# SoC_PWR.net
KiCad netlist of a schematic drawn in Altium Designer
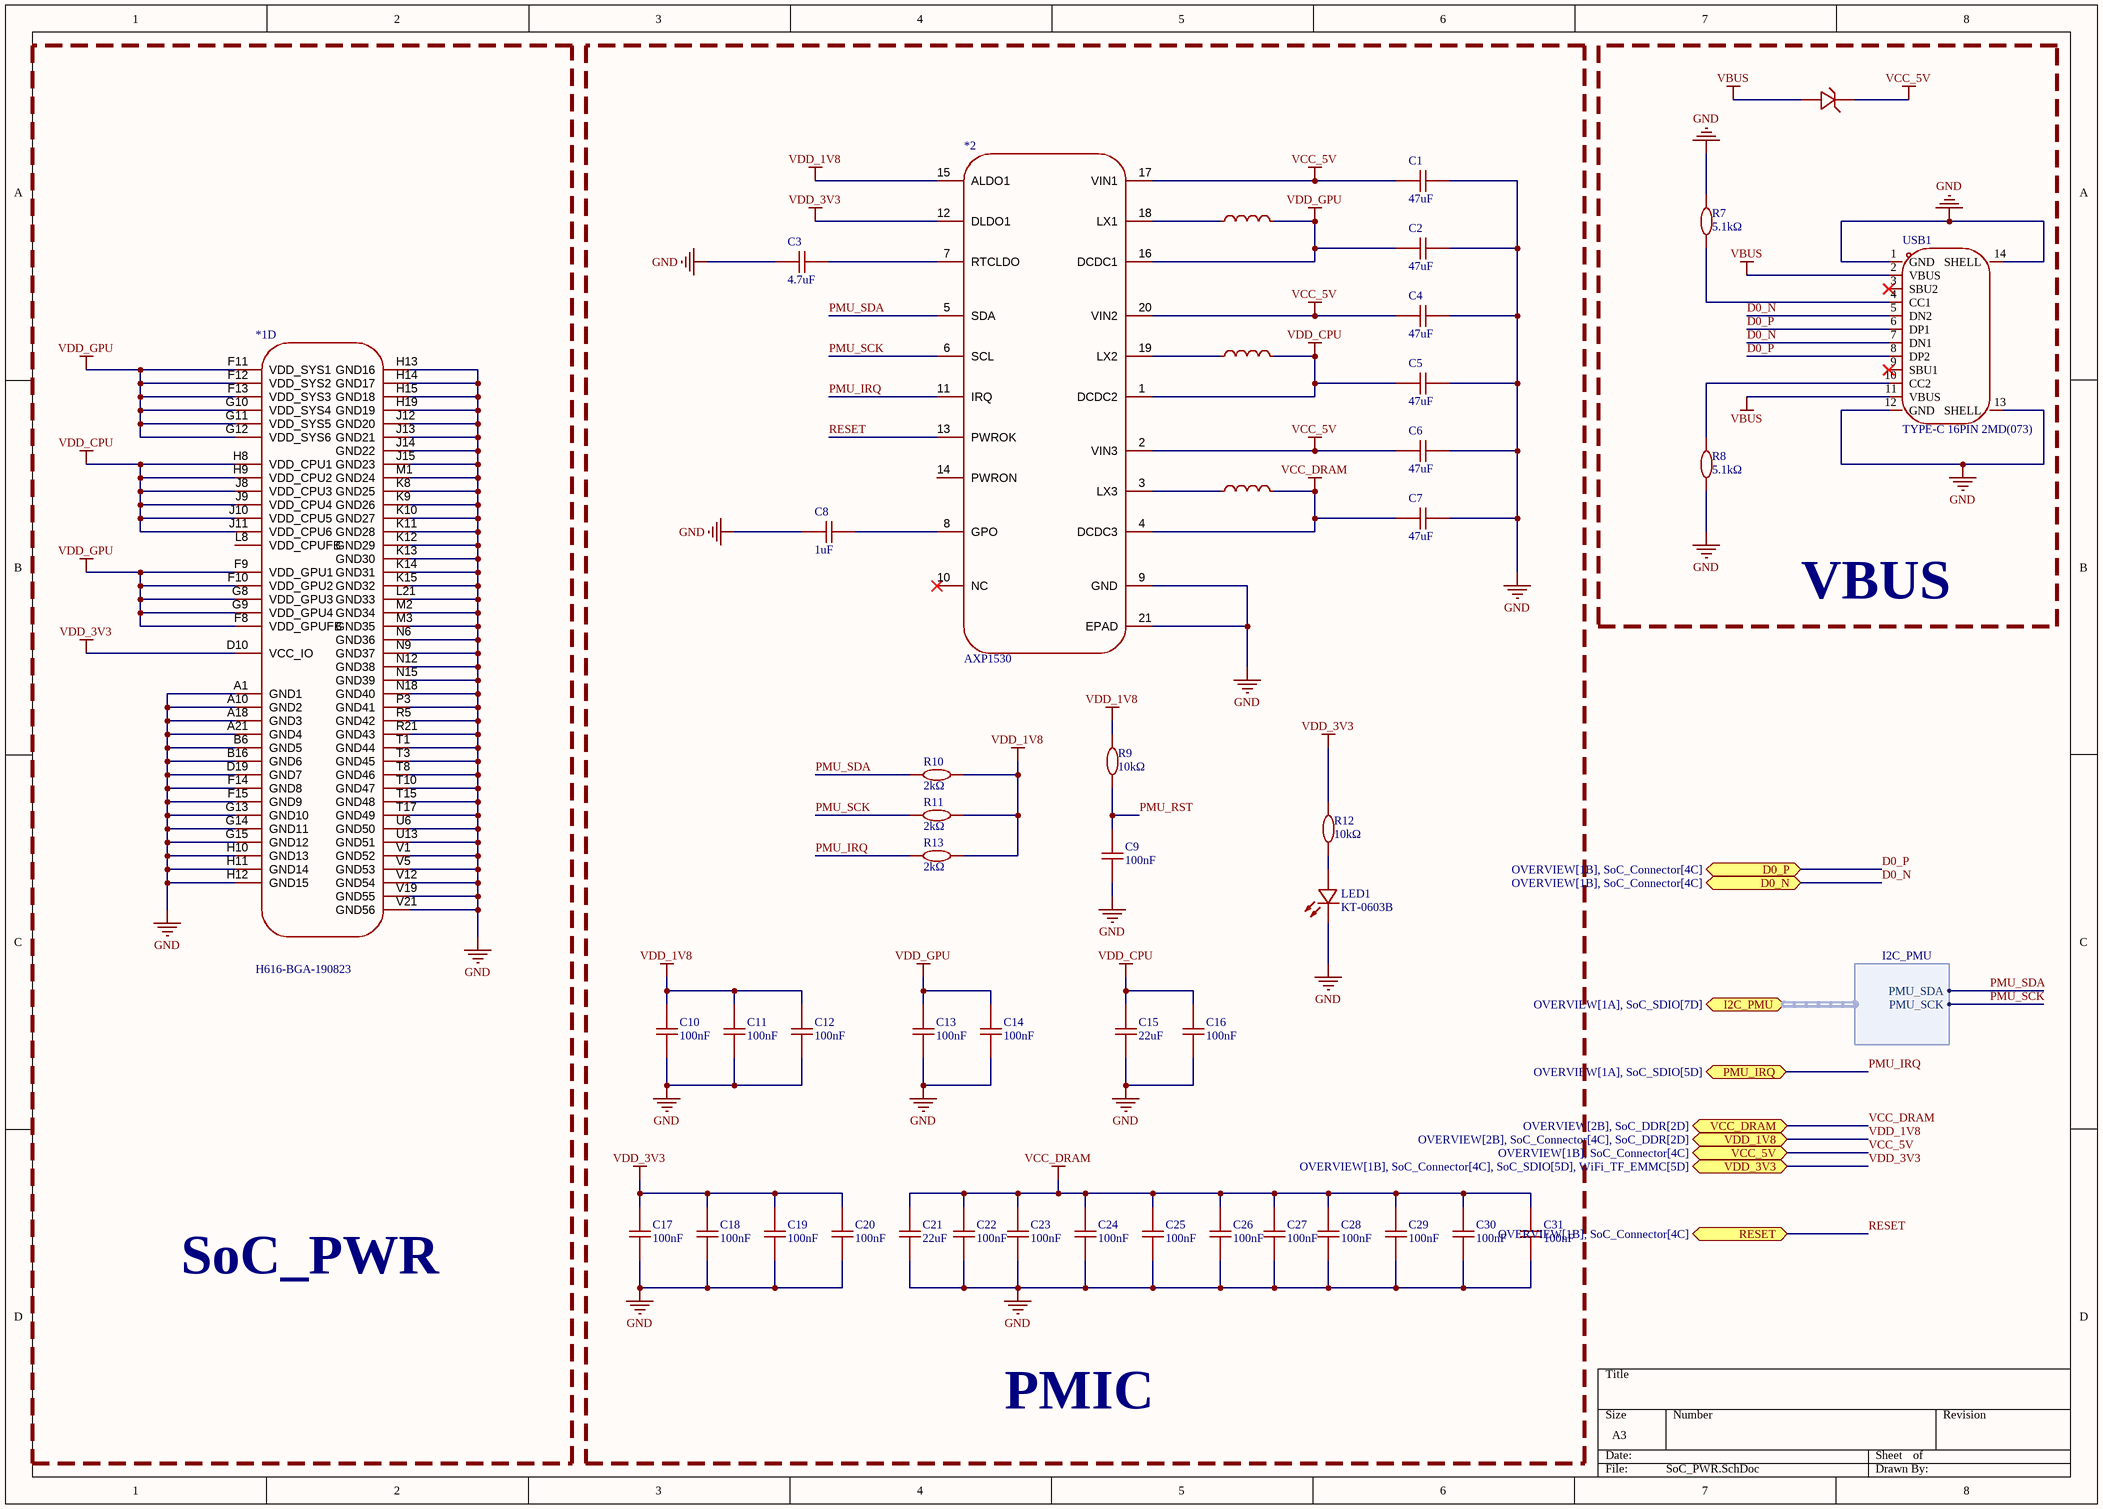
[diagram p0: SoC_PWR.SchDoc]

(export (version "E")
  (design (tool "Eeschema 10.0.6"))
  (components
    (comp (ref "*1")
      (value "H616-BGA-190823")
      (footprint "BGA-284_L14.0-W12.0-P0.65-TL")
      (description "Allwinner H616")
      (libsource (lib "IC") (part "H616-BGA-190823"))
    )
    (comp (ref "*2")
      (value "AXP1530")
      (footprint "QFN-20_L3.0-W3.0-P0.40-BL-EP1.7")
      (description "AXP313A")
      (libsource (lib "IC") (part "AXP1530"))
    )
    (comp (ref "C1")
      (value "47uF")
      (footprint "C0603")
      (description "16V 22uF X5R ±20% 0603 Ceramic Capacitors ROHS")
      (libsource (lib "RLC") (part "47uF"))
    )
    (comp (ref "C2")
      (value "47uF")
      (footprint "C0603")
      (description "16V 22uF X5R ±20% 0603 Ceramic Capacitors ROHS")
      (libsource (lib "RLC") (part "47uF"))
    )
    (comp (ref "C3")
      (value "4.7uF")
      (footprint "C0402")
      (description "10V 4.7uF X5R ±20% 0402 Ceramic Capacitors ROHS")
      (libsource (lib "RLC") (part "4.7uF"))
    )
    (comp (ref "C4")
      (value "47uF")
      (footprint "C0603")
      (description "16V 22uF X5R ±20% 0603 Ceramic Capacitors ROHS")
      (libsource (lib "RLC") (part "47uF"))
    )
    (comp (ref "C5")
      (value "47uF")
      (footprint "C0603")
      (description "16V 22uF X5R ±20% 0603 Ceramic Capacitors ROHS")
      (libsource (lib "RLC") (part "47uF"))
    )
    (comp (ref "C6")
      (value "47uF")
      (footprint "C0603")
      (description "16V 22uF X5R ±20% 0603 Ceramic Capacitors ROHS")
      (libsource (lib "RLC") (part "47uF"))
    )
    (comp (ref "C7")
      (value "47uF")
      (footprint "C0603")
      (description "16V 22uF X5R ±20% 0603 Ceramic Capacitors ROHS")
      (libsource (lib "RLC") (part "47uF"))
    )
    (comp (ref "C8")
      (value "1uF")
      (footprint "C0402")
      (description "50V 1uF X5R ±10% 0402 Ceramic Capacitors ROHS")
      (libsource (lib "RLC") (part "1uF"))
    )
    (comp (ref "C9")
      (value "100nF")
      (footprint "C0402")
      (description "50V 100nF X7R ±10% 0402 Ceramic Capacitors ROHS")
      (libsource (lib "RLC") (part "100nF"))
    )
    (comp (ref "C10")
      (value "100nF")
      (footprint "C0402")
      (description "50V 100nF X7R ±10% 0402 Ceramic Capacitors ROHS")
      (libsource (lib "RLC") (part "100nF"))
    )
    (comp (ref "C11")
      (value "100nF")
      (footprint "C0402")
      (description "50V 100nF X7R ±10% 0402 Ceramic Capacitors ROHS")
      (libsource (lib "RLC") (part "100nF"))
    )
    (comp (ref "C12")
      (value "100nF")
      (footprint "C0402")
      (description "50V 100nF X7R ±10% 0402 Ceramic Capacitors ROHS")
      (libsource (lib "RLC") (part "100nF"))
    )
    (comp (ref "C13")
      (value "100nF")
      (footprint "C0402")
      (description "50V 100nF X7R ±10% 0402 Ceramic Capacitors ROHS")
      (libsource (lib "RLC") (part "100nF"))
    )
    (comp (ref "C14")
      (value "100nF")
      (footprint "C0402")
      (description "50V 100nF X7R ±10% 0402 Ceramic Capacitors ROHS")
      (libsource (lib "RLC") (part "100nF"))
    )
    (comp (ref "C15")
      (value "22uF")
      (footprint "C0603")
      (description "16V 22uF X5R ±20% 0603 Ceramic Capacitors ROHS")
      (libsource (lib "RLC") (part "22uF"))
    )
    (comp (ref "C16")
      (value "100nF")
      (footprint "C0402")
      (description "50V 100nF X7R ±10% 0402 Ceramic Capacitors ROHS")
      (libsource (lib "RLC") (part "100nF"))
    )
    (comp (ref "C17")
      (value "100nF")
      (footprint "C0402")
      (description "50V 100nF X7R ±10% 0402 Ceramic Capacitors ROHS")
      (libsource (lib "RLC") (part "100nF"))
    )
    (comp (ref "C18")
      (value "100nF")
      (footprint "C0402")
      (description "50V 100nF X7R ±10% 0402 Ceramic Capacitors ROHS")
      (libsource (lib "RLC") (part "100nF"))
    )
    (comp (ref "C19")
      (value "100nF")
      (footprint "C0402")
      (description "50V 100nF X7R ±10% 0402 Ceramic Capacitors ROHS")
      (libsource (lib "RLC") (part "100nF"))
    )
    (comp (ref "C20")
      (value "100nF")
      (footprint "C0402")
      (description "50V 100nF X7R ±10% 0402 Ceramic Capacitors ROHS")
      (libsource (lib "RLC") (part "100nF"))
    )
    (comp (ref "C21")
      (value "22uF")
      (footprint "C0603")
      (description "16V 22uF X5R ±20% 0603 Ceramic Capacitors ROHS")
      (libsource (lib "RLC") (part "22uF"))
    )
    (comp (ref "C22")
      (value "100nF")
      (footprint "C0402")
      (description "50V 100nF X7R ±10% 0402 Ceramic Capacitors ROHS")
      (libsource (lib "RLC") (part "100nF"))
    )
    (comp (ref "C23")
      (value "100nF")
      (footprint "C0402")
      (description "50V 100nF X7R ±10% 0402 Ceramic Capacitors ROHS")
      (libsource (lib "RLC") (part "100nF"))
    )
    (comp (ref "C24")
      (value "100nF")
      (footprint "C0402")
      (description "50V 100nF X7R ±10% 0402 Ceramic Capacitors ROHS")
      (libsource (lib "RLC") (part "100nF"))
    )
    (comp (ref "C25")
      (value "100nF")
      (footprint "C0402")
      (description "50V 100nF X7R ±10% 0402 Ceramic Capacitors ROHS")
      (libsource (lib "RLC") (part "100nF"))
    )
    (comp (ref "C26")
      (value "100nF")
      (footprint "C0402")
      (description "50V 100nF X7R ±10% 0402 Ceramic Capacitors ROHS")
      (libsource (lib "RLC") (part "100nF"))
    )
    (comp (ref "C27")
      (value "100nF")
      (footprint "C0402")
      (description "50V 100nF X7R ±10% 0402 Ceramic Capacitors ROHS")
      (libsource (lib "RLC") (part "100nF"))
    )
    (comp (ref "C28")
      (value "100nF")
      (footprint "C0402")
      (description "50V 100nF X7R ±10% 0402 Ceramic Capacitors ROHS")
      (libsource (lib "RLC") (part "100nF"))
    )
    (comp (ref "C29")
      (value "100nF")
      (footprint "C0402")
      (description "50V 100nF X7R ±10% 0402 Ceramic Capacitors ROHS")
      (libsource (lib "RLC") (part "100nF"))
    )
    (comp (ref "C30")
      (value "100nF")
      (footprint "C0402")
      (description "50V 100nF X7R ±10% 0402 Ceramic Capacitors ROHS")
      (libsource (lib "RLC") (part "100nF"))
    )
    (comp (ref "C31")
      (value "100nF")
      (footprint "C0402")
      (description "50V 100nF X7R ±10% 0402 Ceramic Capacitors ROHS")
      (libsource (lib "RLC") (part "100nF"))
    )
    (comp (ref "D1")
      (value "DSK24")
      (footprint "SOD-123FL_L2.7-W1.8-LS3.8-RD")
      (description "电压:40V 电流:2A")
      (fields (field (name "MANUFACTURER") "Littelfuse(美国力特)") (field (name "MANUFACTURER PART") "SMAJ5.0A"))
      (libsource (lib "LED") (part "DSK24"))
    )
    (comp (ref "L1")
      (value "1uH")
      (footprint "IND-SMD_L4.0-W4.0")
      (description "4.15A 1uH ±30% 18mΩ SMD,4x4mm Fixed Inductors ROHS")
      (fields
        (field (name "MANUFACTURER") "Sunltech(顺磁)")
        (field (name "MANUFACTURER PART") "SLW4030S1R0NST")
      )
      (libsource (lib "RLC") (part "SLW4030S1R0NST"))
    )
    (comp (ref "L2")
      (value "1uH")
      (footprint "IND-SMD_L4.0-W4.0")
      (description "4.15A 1uH ±30% 18mΩ SMD,4x4mm Fixed Inductors ROHS")
      (fields
        (field (name "MANUFACTURER") "Sunltech(顺磁)")
        (field (name "MANUFACTURER PART") "SLW4030S1R0NST")
      )
      (libsource (lib "RLC") (part "SLW4030S1R0NST"))
    )
    (comp (ref "L3")
      (value "1uH")
      (footprint "IND-SMD_L4.0-W4.0")
      (description "4.15A 1uH ±30% 18mΩ SMD,4x4mm Fixed Inductors ROHS")
      (fields
        (field (name "MANUFACTURER") "Sunltech(顺磁)")
        (field (name "MANUFACTURER PART") "SLW4030S1R0NST")
      )
      (libsource (lib "RLC") (part "SLW4030S1R0NST"))
    )
    (comp (ref "LED1")
      (value "KT-0603B")
      (footprint "LED0603-BL")
      (description "30mA 2.6V~3.2V Blue 0603 LED Indication - Discrete ROHS")
      (libsource (lib "LED") (part "KT-0603B"))
    )
    (comp (ref "R7")
      (value "5.1kΩ")
      (footprint "R0402")
      (description "5.1kΩ 62.5mW 50V ±100ppm/℃ Thick Film Resistor ±1% 0402 Chip Resistor - Surface Mount ROHS")
      (libsource (lib "RLC") (part "5.1kΩ"))
    )
    (comp (ref "R8")
      (value "5.1kΩ")
      (footprint "R0402")
      (description "5.1kΩ 62.5mW 50V ±100ppm/℃ Thick Film Resistor ±1% 0402 Chip Resistor - Surface Mount ROHS")
      (libsource (lib "RLC") (part "5.1kΩ"))
    )
    (comp (ref "R9")
      (value "10kΩ")
      (footprint "R0402")
      (description "62.5mW 10kΩ 50V ±100ppm/℃ Thick Film Resistor ±1% 0402 Chip Resistor - Surface Mount ROHS")
      (libsource (lib "RLC") (part "10kΩ"))
    )
    (comp (ref "R10")
      (value "2kΩ")
      (footprint "R0402")
      (description "100mW 2kΩ 75V ±100ppm/℃ Thick Film Resistor ±1% 0402 Chip Resistor - Surface Mount ROHS")
      (libsource (lib "RLC") (part "2kΩ"))
    )
    (comp (ref "R11")
      (value "2kΩ")
      (footprint "R0402")
      (description "100mW 2kΩ 75V ±100ppm/℃ Thick Film Resistor ±1% 0402 Chip Resistor - Surface Mount ROHS")
      (libsource (lib "RLC") (part "2kΩ"))
    )
    (comp (ref "R12")
      (value "10kΩ")
      (footprint "R0402")
      (description "62.5mW 10kΩ 50V ±100ppm/℃ Thick Film Resistor ±1% 0402 Chip Resistor - Surface Mount ROHS")
      (libsource (lib "RLC") (part "10kΩ"))
    )
    (comp (ref "R13")
      (value "2kΩ")
      (footprint "R0402")
      (description "100mW 2kΩ 75V ±100ppm/℃ Thick Film Resistor ±1% 0402 Chip Resistor - Surface Mount ROHS")
      (libsource (lib "RLC") (part "2kΩ"))
    )
    (comp (ref "USB1")
      (value "TYPE-C 16PIN 2MD(073)")
      (footprint "USB-C-SMD_TYPE-C-6PIN-2MD-073")
      (description "16pin type-c")
      (libsource (lib "Connector") (part "TYPE-C 16PIN 2MD(073)"))
    )
  )
  (nets
    (net (code "2") (name "/D0_N") (class "Default")
      (node (ref "USB1") (pin "5") (pinfunction "DN2_5") (pintype "passive"))
      (node (ref "USB1") (pin "7") (pinfunction "DN1_7") (pintype "passive"))
    )
    (net (code "3") (name "/D0_P") (class "Default")
      (node (ref "USB1") (pin "6") (pinfunction "DP1_6") (pintype "passive"))
      (node (ref "USB1") (pin "8") (pinfunction "DP2_8") (pintype "passive"))
    )
    (net (code "4") (name "/PMU_IRQ") (class "Default")
      (node (ref "*2") (pin "11") (pinfunction "IRQ_11") (pintype "passive"))
      (node (ref "R13") (pin "1") (pinfunction "1_1") (pintype "passive"))
    )
    (net (code "5") (name "/PMU_RST") (class "Default")
      (node (ref "C9") (pin "2") (pinfunction "2_2") (pintype "passive"))
      (node (ref "R9") (pin "1") (pinfunction "1_1") (pintype "passive"))
    )
    (net (code "6") (name "/PMU_SCK") (class "Default")
      (node (ref "*2") (pin "6") (pinfunction "SCL_6") (pintype "passive"))
      (node (ref "R11") (pin "1") (pinfunction "1_1") (pintype "passive"))
    )
    (net (code "7") (name "/PMU_SDA") (class "Default")
      (node (ref "*2") (pin "5") (pinfunction "SDA_5") (pintype "passive"))
      (node (ref "R10") (pin "1") (pinfunction "1_1") (pintype "passive"))
    )
    (net (code "8") (name "/RESET") (class "Default")
      (node (ref "*2") (pin "13") (pinfunction "PWROK_13") (pintype "passive"))
    )
    (net (code "10") (name "GND") (class "Default")
      (node (ref "*1") (pin "A1") (pinfunction "GND1_A1") (pintype "passive"))
      (node (ref "*1") (pin "A10") (pinfunction "GND2_A10") (pintype "passive"))
      (node (ref "*1") (pin "A18") (pinfunction "GND3_A18") (pintype "passive"))
      (node (ref "*1") (pin "A21") (pinfunction "GND4_A21") (pintype "passive"))
      (node (ref "*1") (pin "B16") (pinfunction "GND6_B16") (pintype "passive"))
      (node (ref "*1") (pin "B6") (pinfunction "GND5_B6") (pintype "passive"))
      (node (ref "*1") (pin "D19") (pinfunction "GND7_D19") (pintype "passive"))
      (node (ref "*1") (pin "F14") (pinfunction "GND8_F14") (pintype "passive"))
      (node (ref "*1") (pin "F15") (pinfunction "GND9_F15") (pintype "passive"))
      (node (ref "*1") (pin "G13") (pinfunction "GND10_G13") (pintype "passive"))
      (node (ref "*1") (pin "G14") (pinfunction "GND11_G14") (pintype "passive"))
      (node (ref "*1") (pin "G15") (pinfunction "GND12_G15") (pintype "passive"))
      (node (ref "*1") (pin "H10") (pinfunction "GND13_H10") (pintype "passive"))
      (node (ref "*1") (pin "H11") (pinfunction "GND14_H11") (pintype "passive"))
      (node (ref "*1") (pin "H12") (pinfunction "GND15_H12") (pintype "passive"))
      (node (ref "*1") (pin "H13") (pinfunction "GND16_H13") (pintype "passive"))
      (node (ref "*1") (pin "H14") (pinfunction "GND17_H14") (pintype "passive"))
      (node (ref "*1") (pin "H15") (pinfunction "GND18_H15") (pintype "passive"))
      (node (ref "*1") (pin "H19") (pinfunction "GND19_H19") (pintype "passive"))
      (node (ref "*1") (pin "J12") (pinfunction "GND20_J12") (pintype "passive"))
      (node (ref "*1") (pin "J13") (pinfunction "GND21_J13") (pintype "passive"))
      (node (ref "*1") (pin "J14") (pinfunction "GND22_J14") (pintype "passive"))
      (node (ref "*1") (pin "J15") (pinfunction "GND23_J15") (pintype "passive"))
      (node (ref "*1") (pin "K10") (pinfunction "GND27_K10") (pintype "passive"))
      (node (ref "*1") (pin "K11") (pinfunction "GND28_K11") (pintype "passive"))
      (node (ref "*1") (pin "K12") (pinfunction "GND29_K12") (pintype "passive"))
      (node (ref "*1") (pin "K13") (pinfunction "GND30_K13") (pintype "passive"))
      (node (ref "*1") (pin "K14") (pinfunction "GND31_K14") (pintype "passive"))
      (node (ref "*1") (pin "K15") (pinfunction "GND32_K15") (pintype "passive"))
      (node (ref "*1") (pin "K8") (pinfunction "GND25_K8") (pintype "passive"))
      (node (ref "*1") (pin "K9") (pinfunction "GND26_K9") (pintype "passive"))
      (node (ref "*1") (pin "L21") (pinfunction "GND33_L21") (pintype "passive"))
      (node (ref "*1") (pin "M1") (pinfunction "GND24_M1") (pintype "passive"))
      (node (ref "*1") (pin "M2") (pinfunction "GND34_M2") (pintype "passive"))
      (node (ref "*1") (pin "M3") (pinfunction "GND35_M3") (pintype "passive"))
      (node (ref "*1") (pin "N12") (pinfunction "GND38_N12") (pintype "passive"))
      (node (ref "*1") (pin "N15") (pinfunction "GND39_N15") (pintype "passive"))
      (node (ref "*1") (pin "N18") (pinfunction "GND40_N18") (pintype "passive"))
      (node (ref "*1") (pin "N6") (pinfunction "GND36_N6") (pintype "passive"))
      (node (ref "*1") (pin "N9") (pinfunction "GND37_N9") (pintype "passive"))
      (node (ref "*1") (pin "P3") (pinfunction "GND41_P3") (pintype "passive"))
      (node (ref "*1") (pin "R21") (pinfunction "GND43_R21") (pintype "passive"))
      (node (ref "*1") (pin "R5") (pinfunction "GND42_R5") (pintype "passive"))
      (node (ref "*1") (pin "T1") (pinfunction "GND44_T1") (pintype "passive"))
      (node (ref "*1") (pin "T10") (pinfunction "GND47_T10") (pintype "passive"))
      (node (ref "*1") (pin "T15") (pinfunction "GND48_T15") (pintype "passive"))
      (node (ref "*1") (pin "T17") (pinfunction "GND49_T17") (pintype "passive"))
      (node (ref "*1") (pin "T3") (pinfunction "GND45_T3") (pintype "passive"))
      (node (ref "*1") (pin "T8") (pinfunction "GND46_T8") (pintype "passive"))
      (node (ref "*1") (pin "U13") (pinfunction "GND51_U13") (pintype "passive"))
      (node (ref "*1") (pin "U6") (pinfunction "GND50_U6") (pintype "passive"))
      (node (ref "*1") (pin "V1") (pinfunction "GND52_V1") (pintype "passive"))
      (node (ref "*1") (pin "V12") (pinfunction "GND54_V12") (pintype "passive"))
      (node (ref "*1") (pin "V19") (pinfunction "GND55_V19") (pintype "passive"))
      (node (ref "*1") (pin "V21") (pinfunction "GND56_V21") (pintype "passive"))
      (node (ref "*1") (pin "V5") (pinfunction "GND53_V5") (pintype "passive"))
      (node (ref "*2") (pin "21") (pinfunction "EPAD_21") (pintype "passive"))
      (node (ref "*2") (pin "9") (pinfunction "GND_9") (pintype "passive"))
      (node (ref "C1") (pin "2") (pinfunction "2_2") (pintype "passive"))
      (node (ref "C10") (pin "1") (pinfunction "1_1") (pintype "passive"))
      (node (ref "C11") (pin "1") (pinfunction "1_1") (pintype "passive"))
      (node (ref "C12") (pin "1") (pinfunction "1_1") (pintype "passive"))
      (node (ref "C13") (pin "1") (pinfunction "1_1") (pintype "passive"))
      (node (ref "C14") (pin "1") (pinfunction "1_1") (pintype "passive"))
      (node (ref "C15") (pin "1") (pinfunction "1_1") (pintype "passive"))
      (node (ref "C16") (pin "1") (pinfunction "1_1") (pintype "passive"))
      (node (ref "C17") (pin "1") (pinfunction "1_1") (pintype "passive"))
      (node (ref "C18") (pin "1") (pinfunction "1_1") (pintype "passive"))
      (node (ref "C19") (pin "1") (pinfunction "1_1") (pintype "passive"))
      (node (ref "C2") (pin "2") (pinfunction "2_2") (pintype "passive"))
      (node (ref "C20") (pin "1") (pinfunction "1_1") (pintype "passive"))
      (node (ref "C21") (pin "1") (pinfunction "1_1") (pintype "passive"))
      (node (ref "C22") (pin "1") (pinfunction "1_1") (pintype "passive"))
      (node (ref "C23") (pin "1") (pinfunction "1_1") (pintype "passive"))
      (node (ref "C24") (pin "1") (pinfunction "1_1") (pintype "passive"))
      (node (ref "C25") (pin "1") (pinfunction "1_1") (pintype "passive"))
      (node (ref "C26") (pin "1") (pinfunction "1_1") (pintype "passive"))
      (node (ref "C27") (pin "1") (pinfunction "1_1") (pintype "passive"))
      (node (ref "C28") (pin "1") (pinfunction "1_1") (pintype "passive"))
      (node (ref "C29") (pin "1") (pinfunction "1_1") (pintype "passive"))
      (node (ref "C3") (pin "1") (pinfunction "1_1") (pintype "passive"))
      (node (ref "C30") (pin "1") (pinfunction "1_1") (pintype "passive"))
      (node (ref "C31") (pin "1") (pinfunction "1_1") (pintype "passive"))
      (node (ref "C4") (pin "2") (pinfunction "2_2") (pintype "passive"))
      (node (ref "C5") (pin "2") (pinfunction "2_2") (pintype "passive"))
      (node (ref "C6") (pin "2") (pinfunction "2_2") (pintype "passive"))
      (node (ref "C7") (pin "2") (pinfunction "2_2") (pintype "passive"))
      (node (ref "C8") (pin "1") (pinfunction "1_1") (pintype "passive"))
      (node (ref "C9") (pin "1") (pinfunction "1_1") (pintype "passive"))
      (node (ref "LED1") (pin "1") (pinfunction "K_1") (pintype "passive"))
      (node (ref "R7") (pin "2") (pinfunction "2_2") (pintype "passive"))
      (node (ref "R8") (pin "2") (pinfunction "2_2") (pintype "passive"))
      (node (ref "USB1") (pin "1") (pinfunction "GND_1") (pintype "passive"))
      (node (ref "USB1") (pin "12") (pinfunction "GND_12") (pintype "passive"))
      (node (ref "USB1") (pin "13") (pinfunction "SHELL_13") (pintype "passive"))
      (node (ref "USB1") (pin "14") (pinfunction "SHELL_14") (pintype "passive"))
    )
    (net (code "11") (name "Net-(*2-GPO)") (class "Default")
      (node (ref "*2") (pin "8") (pinfunction "GPO_8") (pintype "passive"))
      (node (ref "C8") (pin "2") (pinfunction "2_2") (pintype "passive"))
    )
    (net (code "12") (name "Net-(*2-LX1)") (class "Default")
      (node (ref "*2") (pin "18") (pinfunction "LX1_18") (pintype "passive"))
      (node (ref "L1") (pin "1") (pinfunction "1_1") (pintype "passive"))
    )
    (net (code "13") (name "Net-(*2-LX2)") (class "Default")
      (node (ref "*2") (pin "19") (pinfunction "LX2_19") (pintype "passive"))
      (node (ref "L2") (pin "1") (pinfunction "1_1") (pintype "passive"))
    )
    (net (code "14") (name "Net-(*2-LX3)") (class "Default")
      (node (ref "*2") (pin "3") (pinfunction "LX3_3") (pintype "passive"))
      (node (ref "L3") (pin "1") (pinfunction "1_1") (pintype "passive"))
    )
    (net (code "15") (name "Net-(*2-RTCLDO)") (class "Default")
      (node (ref "*2") (pin "7") (pinfunction "RTCLDO_7") (pintype "passive"))
      (node (ref "C3") (pin "2") (pinfunction "2_2") (pintype "passive"))
    )
    (net (code "16") (name "Net-(LED1-A)") (class "Default")
      (node (ref "LED1") (pin "2") (pinfunction "A_2") (pintype "passive"))
      (node (ref "R12") (pin "1") (pinfunction "1_1") (pintype "passive"))
    )
    (net (code "17") (name "Net-(USB1-CC1)") (class "Default")
      (node (ref "R7") (pin "1") (pinfunction "1_1") (pintype "passive"))
      (node (ref "USB1") (pin "4") (pinfunction "CC1_4") (pintype "passive"))
    )
    (net (code "18") (name "Net-(USB1-CC2)") (class "Default")
      (node (ref "R8") (pin "1") (pinfunction "1_1") (pintype "passive"))
      (node (ref "USB1") (pin "10") (pinfunction "CC2_10") (pintype "passive"))
    )
    (net (code "19") (name "VBUS") (class "Default")
      (node (ref "D1") (pin "2") (pinfunction "A_2") (pintype "passive"))
      (node (ref "USB1") (pin "11") (pinfunction "VBUS_11") (pintype "passive"))
      (node (ref "USB1") (pin "2") (pinfunction "VBUS_2") (pintype "passive"))
    )
    (net (code "20") (name "VCC_5V") (class "Default")
      (node (ref "*2") (pin "17") (pinfunction "VIN1_17") (pintype "passive"))
      (node (ref "*2") (pin "2") (pinfunction "VIN3_2") (pintype "passive"))
      (node (ref "*2") (pin "20") (pinfunction "VIN2_20") (pintype "passive"))
      (node (ref "C1") (pin "1") (pinfunction "1_1") (pintype "passive"))
      (node (ref "C4") (pin "1") (pinfunction "1_1") (pintype "passive"))
      (node (ref "C6") (pin "1") (pinfunction "1_1") (pintype "passive"))
      (node (ref "D1") (pin "1") (pinfunction "C_1") (pintype "passive"))
    )
    (net (code "21") (name "VCC_DRAM") (class "Default")
      (node (ref "*2") (pin "4") (pinfunction "DCDC3_4") (pintype "passive"))
      (node (ref "C21") (pin "2") (pinfunction "2_2") (pintype "passive"))
      (node (ref "C22") (pin "2") (pinfunction "2_2") (pintype "passive"))
      (node (ref "C23") (pin "2") (pinfunction "2_2") (pintype "passive"))
      (node (ref "C24") (pin "2") (pinfunction "2_2") (pintype "passive"))
      (node (ref "C25") (pin "2") (pinfunction "2_2") (pintype "passive"))
      (node (ref "C26") (pin "2") (pinfunction "2_2") (pintype "passive"))
      (node (ref "C27") (pin "2") (pinfunction "2_2") (pintype "passive"))
      (node (ref "C28") (pin "2") (pinfunction "2_2") (pintype "passive"))
      (node (ref "C29") (pin "2") (pinfunction "2_2") (pintype "passive"))
      (node (ref "C30") (pin "2") (pinfunction "2_2") (pintype "passive"))
      (node (ref "C31") (pin "2") (pinfunction "2_2") (pintype "passive"))
      (node (ref "C7") (pin "1") (pinfunction "1_1") (pintype "passive"))
      (node (ref "L3") (pin "2") (pinfunction "2_2") (pintype "passive"))
    )
    (net (code "22") (name "VDD_1V8") (class "Default")
      (node (ref "*2") (pin "15") (pinfunction "ALDO1_15") (pintype "passive"))
      (node (ref "C10") (pin "2") (pinfunction "2_2") (pintype "passive"))
      (node (ref "C11") (pin "2") (pinfunction "2_2") (pintype "passive"))
      (node (ref "C12") (pin "2") (pinfunction "2_2") (pintype "passive"))
      (node (ref "R10") (pin "2") (pinfunction "2_2") (pintype "passive"))
      (node (ref "R11") (pin "2") (pinfunction "2_2") (pintype "passive"))
      (node (ref "R13") (pin "2") (pinfunction "2_2") (pintype "passive"))
      (node (ref "R9") (pin "2") (pinfunction "2_2") (pintype "passive"))
    )
    (net (code "23") (name "VDD_3V3") (class "Default")
      (node (ref "*1") (pin "D10") (pinfunction "VCC_IO_D10") (pintype "passive"))
      (node (ref "*2") (pin "12") (pinfunction "DLDO1_12") (pintype "passive"))
      (node (ref "C17") (pin "2") (pinfunction "2_2") (pintype "passive"))
      (node (ref "C18") (pin "2") (pinfunction "2_2") (pintype "passive"))
      (node (ref "C19") (pin "2") (pinfunction "2_2") (pintype "passive"))
      (node (ref "C20") (pin "2") (pinfunction "2_2") (pintype "passive"))
      (node (ref "R12") (pin "2") (pinfunction "2_2") (pintype "passive"))
    )
    (net (code "24") (name "VDD_CPU") (class "Default")
      (node (ref "*1") (pin "H8") (pinfunction "VDD_CPU1_H8") (pintype "passive"))
      (node (ref "*1") (pin "H9") (pinfunction "VDD_CPU2_H9") (pintype "passive"))
      (node (ref "*1") (pin "J10") (pinfunction "VDD_CPU5_J10") (pintype "passive"))
      (node (ref "*1") (pin "J11") (pinfunction "VDD_CPU6_J11") (pintype "passive"))
      (node (ref "*1") (pin "J8") (pinfunction "VDD_CPU3_J8") (pintype "passive"))
      (node (ref "*1") (pin "J9") (pinfunction "VDD_CPU4_J9") (pintype "passive"))
      (node (ref "*2") (pin "1") (pinfunction "DCDC2_1") (pintype "passive"))
      (node (ref "C15") (pin "2") (pinfunction "2_2") (pintype "passive"))
      (node (ref "C16") (pin "2") (pinfunction "2_2") (pintype "passive"))
      (node (ref "C5") (pin "1") (pinfunction "1_1") (pintype "passive"))
      (node (ref "L2") (pin "2") (pinfunction "2_2") (pintype "passive"))
    )
    (net (code "25") (name "VDD_GPU") (class "Default")
      (node (ref "*1") (pin "F10") (pinfunction "VDD_GPU2_F10") (pintype "passive"))
      (node (ref "*1") (pin "F11") (pinfunction "VDD_SYS1_F11") (pintype "passive"))
      (node (ref "*1") (pin "F12") (pinfunction "VDD_SYS2_F12") (pintype "passive"))
      (node (ref "*1") (pin "F13") (pinfunction "VDD_SYS3_F13") (pintype "passive"))
      (node (ref "*1") (pin "F8") (pinfunction "VDD_GPUFB_F8") (pintype "passive"))
      (node (ref "*1") (pin "F9") (pinfunction "VDD_GPU1_F9") (pintype "passive"))
      (node (ref "*1") (pin "G10") (pinfunction "VDD_SYS4_G10") (pintype "passive"))
      (node (ref "*1") (pin "G11") (pinfunction "VDD_SYS5_G11") (pintype "passive"))
      (node (ref "*1") (pin "G12") (pinfunction "VDD_SYS6_G12") (pintype "passive"))
      (node (ref "*1") (pin "G8") (pinfunction "VDD_GPU3_G8") (pintype "passive"))
      (node (ref "*1") (pin "G9") (pinfunction "VDD_GPU4_G9") (pintype "passive"))
      (node (ref "*2") (pin "16") (pinfunction "DCDC1_16") (pintype "passive"))
      (node (ref "C13") (pin "2") (pinfunction "2_2") (pintype "passive"))
      (node (ref "C14") (pin "2") (pinfunction "2_2") (pintype "passive"))
      (node (ref "C2") (pin "1") (pinfunction "1_1") (pintype "passive"))
      (node (ref "L1") (pin "2") (pinfunction "2_2") (pintype "passive"))
    )
    (net (code "26") (name "unconnected-(*1D-VDD_CPUFB-PadL8)") (class "Default")
      (node (ref "*1") (pin "L8") (pinfunction "VDD_CPUFB_L8") (pintype "passive"))
    )
    (net (code "27") (name "unconnected-(*2-NC-Pad10)") (class "Default")
      (node (ref "*2") (pin "10") (pinfunction "NC_10") (pintype "passive+no_connect"))
    )
    (net (code "28") (name "unconnected-(*2-PWRON-Pad14)") (class "Default")
      (node (ref "*2") (pin "14") (pinfunction "PWRON_14") (pintype "passive"))
    )
    (net (code "29") (name "unconnected-(USB1-SBU1-Pad9)") (class "Default")
      (node (ref "USB1") (pin "9") (pinfunction "SBU1_9") (pintype "passive+no_connect"))
    )
    (net (code "30") (name "unconnected-(USB1-SBU2-Pad3)") (class "Default")
      (node (ref "USB1") (pin "3") (pinfunction "SBU2_3") (pintype "passive+no_connect"))
    )
  )
)
